# Moo_Digital.net
KiCad netlist of a schematic drawn in Altium Designer
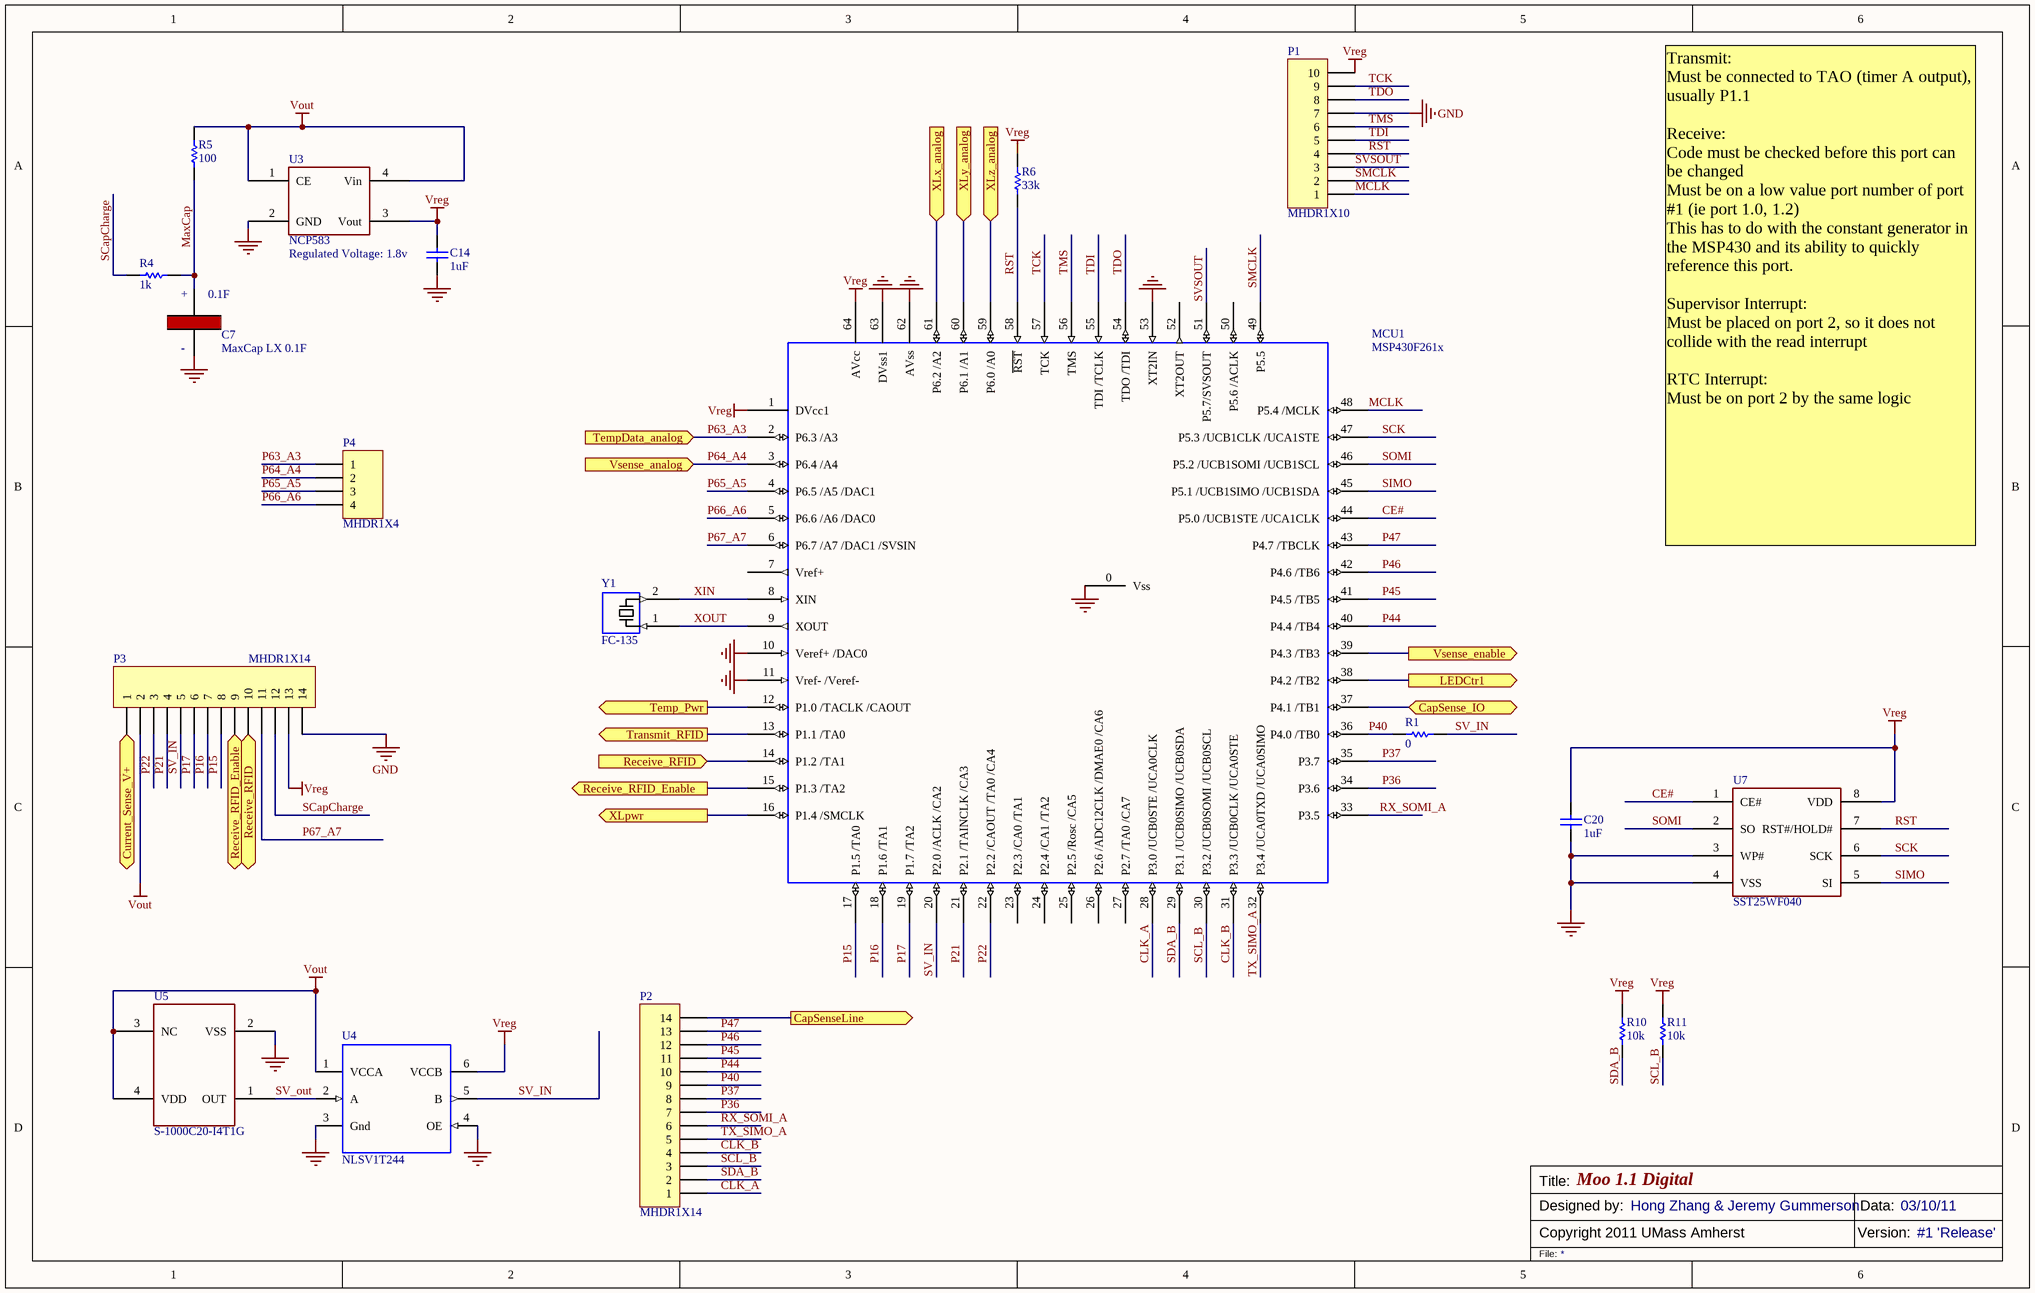
[diagram p0: Moo_Digital.SchDoc]

(export (version "E")
  (design (tool "Eeschema 10.0.6"))
  (components
    (comp (ref "C7")
      (value "MaxCap LX 0.1F")
      (footprint "Maxcap LX 0.1F")
      (description "MaxCap LX 0.1F, low leakage supper cap 5.5v")
      (libsource (lib "WispLib") (part "MaxCap LX 0.1F"))
    )
    (comp (ref "C14")
      (value "1uF")
      (footprint "WispLib:0402")
      (description "Ceramic Capacitor - Standard")
      (fields (field (name "Comment") "Ceramic_Chip_Capacitor"))
      (libsource (lib "WispLib") (part "Ceramic_Chip_Capacitor"))
    )
    (comp (ref "C20")
      (value "1uF")
      (footprint "WispLib:0402")
      (description "Ceramic Capacitor - Standard")
      (fields (field (name "Comment") "Ceramic_Chip_Capacitor"))
      (libsource (lib "WispLib") (part "Ceramic_Chip_Capacitor"))
    )
    (comp (ref "MCU1")
      (value "MSP430F261x")
      (footprint "64-PM")
      (description "64PM MSP430F261x")
      (libsource (lib "WispLib") (part "MSP430F261x"))
    )
    (comp (ref "P1")
      (value "MHDR1X10")
      (footprint "MHDR1X10")
      (description "Header, 10-Pin")
      (fields (field (name "PUBLISHER") "Altium Limited"))
      (libsource (lib "Miscellaneous Connectors") (part "MHDR1X10"))
    )
    (comp (ref "P2")
      (value "MHDR1X14")
      (footprint "MHDR1X14")
      (description "Header, 14-Pin")
      (fields (field (name "PUBLISHER") "Altium Limited"))
      (libsource (lib "") (part "MHDR1X14_1"))
    )
    (comp (ref "P3")
      (value "MHDR1X14")
      (footprint "MHDR1X14")
      (description "Header, 14-Pin")
      (fields (field (name "PUBLISHER") "Altium Limited"))
      (libsource (lib "Miscellaneous Connectors") (part "MHDR1X14"))
    )
    (comp (ref "P4")
      (value "MHDR1X4")
      (footprint "MHDR1X4")
      (description "Header, 4-Pin")
      (fields (field (name "PUBLISHER") "Altium Limited"))
      (libsource (lib "Miscellaneous Connectors") (part "MHDR1X4"))
    )
    (comp (ref "R1")
      (value "0")
      (footprint "WispLib:0402")
      (description "Thick Film Chip Resistor")
      (libsource (lib "*") (part "Thick Film Chip Resistor"))
    )
    (comp (ref "R4")
      (value "1k")
      (footprint "WispLib:0402")
      (description "Thick Film Chip Resistor")
      (libsource (lib "*") (part "Thick Film Chip Resistor"))
    )
    (comp (ref "R5")
      (value "100")
      (footprint "WispLib:0402")
      (description "Thick Film Chip Resistor")
      (libsource (lib "*") (part "Thick Film Chip Resistor"))
    )
    (comp (ref "R6")
      (value "33k")
      (footprint "WispLib:0402")
      (description "Thick Film Chip Resistor")
      (libsource (lib "*") (part "Thick Film Chip Resistor"))
    )
    (comp (ref "R10")
      (value "10k")
      (footprint "WispLib:0402")
      (description "Thick Film Chip Resistor")
      (libsource (lib "*") (part "Thick Film Chip Resistor"))
    )
    (comp (ref "R11")
      (value "10k")
      (footprint "WispLib:0402")
      (description "Thick Film Chip Resistor")
      (libsource (lib "*") (part "Thick Film Chip Resistor"))
    )
    (comp (ref "U3")
      (value "NCP583")
      (footprint "SC82-AB")
      (description "Ultra-Low Iq 150mA CMOS LDO Regulator with Enable")
      (fields (field (name "REGULATED VOLTAGE") "1.8v"))
      (libsource (lib "*") (part "NCP583"))
    )
    (comp (ref "U4")
      (value "NLSV1T244")
      (footprint "UDFN6")
      (description "Level Shifter: 1-Bit Dual-Supply Non-Inverting Level Translator")
      (fields (field (name "PART NUMBER") "ADG3301"))
      (libsource (lib "WispLib") (part "NLSV1T244"))
    )
    (comp (ref "U5")
      (value "S-1000C20-I4T1G")
      (footprint "SNT-4A")
      (libsource (lib "WispLib") (part "S-1000C20-I4T"))
    )
    (comp (ref "U7")
      (value "SST25WF040")
      (footprint "SOIC8")
      (description "Serial Flash Memory - 8 Lead SOIC Package")
      (libsource (lib "WispLib") (part "SST25WF040"))
    )
    (comp (ref "Y1") (value "FC-135") (footprint "FC-135") (libsource (lib "WispLib") (part "FC-135")))
  )
  (nets
    (net (code "1") (name "/CE#") (class "Default")
      (node (ref "MCU1") (pin "44") (pinfunction "P5.0_/UCB1STE_/UCA1CLK_44") (pintype "bidirectional"))
      (node (ref "U7") (pin "1") (pinfunction "CE#_1") (pintype "passive"))
    )
    (net (code "2") (name "/CLK_A") (class "Default")
      (node (ref "MCU1") (pin "28") (pinfunction "P3.0_/UCB0STE_/UCA0CLK_28") (pintype "bidirectional"))
      (node (ref "P2") (pin "1") (pinfunction "1_1") (pintype "passive"))
    )
    (net (code "3") (name "/CLK_B") (class "Default")
      (node (ref "MCU1") (pin "31") (pinfunction "P3.3_/UCB0CLK_/UCA0STE_31") (pintype "bidirectional"))
      (node (ref "P2") (pin "4") (pinfunction "4_4") (pintype "passive"))
    )
    (net (code "4") (name "/CapSenseLine") (class "Default")
      (node (ref "P2") (pin "14") (pinfunction "14_14") (pintype "passive"))
    )
    (net (code "5") (name "/CapSense_IO") (class "Default")
      (node (ref "MCU1") (pin "37") (pinfunction "P4.1_/TB1_37") (pintype "bidirectional"))
    )
    (net (code "6") (name "/Current_Sense_V+") (class "Default")
      (node (ref "P3") (pin "1") (pinfunction "1_1") (pintype "passive"))
    )
    (net (code "7") (name "/LEDCtr1") (class "Default")
      (node (ref "MCU1") (pin "38") (pinfunction "P4.2_/TB2_38") (pintype "bidirectional"))
    )
    (net (code "8") (name "/MCLK") (class "Default")
      (node (ref "MCU1") (pin "48") (pinfunction "P5.4_/MCLK_48") (pintype "bidirectional"))
      (node (ref "P1") (pin "1") (pinfunction "1_1") (pintype "passive"))
    )
    (net (code "9") (name "/MaxCap") (class "Default")
      (node (ref "C7") (pin "1") (pinfunction "Positive_1") (pintype "power_in"))
      (node (ref "R4") (pin "1") (pinfunction "1_1") (pintype "passive"))
      (node (ref "R5") (pin "1") (pinfunction "1_1") (pintype "passive"))
    )
    (net (code "10") (name "/P15") (class "Default")
      (node (ref "MCU1") (pin "17") (pinfunction "P1.5_/TA0_17") (pintype "bidirectional"))
      (node (ref "P3") (pin "8") (pinfunction "8_8") (pintype "passive"))
    )
    (net (code "11") (name "/P16") (class "Default")
      (node (ref "MCU1") (pin "18") (pinfunction "P1.6_/TA1_18") (pintype "bidirectional"))
      (node (ref "P3") (pin "7") (pinfunction "7_7") (pintype "passive"))
    )
    (net (code "12") (name "/P17") (class "Default")
      (node (ref "MCU1") (pin "19") (pinfunction "P1.7_/TA2_19") (pintype "bidirectional"))
      (node (ref "P3") (pin "6") (pinfunction "6_6") (pintype "passive"))
    )
    (net (code "13") (name "/P21") (class "Default")
      (node (ref "MCU1") (pin "21") (pinfunction "P2.1_/TAINCLK_/CA3_21") (pintype "bidirectional"))
      (node (ref "P3") (pin "4") (pinfunction "4_4") (pintype "passive"))
    )
    (net (code "14") (name "/P22") (class "Default")
      (node (ref "MCU1") (pin "22") (pinfunction "P2.2_/CAOUT_/TA0_/CA4_22") (pintype "bidirectional"))
      (node (ref "P3") (pin "3") (pinfunction "3_3") (pintype "passive"))
    )
    (net (code "15") (name "/P36") (class "Default")
      (node (ref "MCU1") (pin "34") (pinfunction "P3.6_34") (pintype "bidirectional"))
      (node (ref "P2") (pin "7") (pinfunction "7_7") (pintype "passive"))
    )
    (net (code "16") (name "/P37") (class "Default")
      (node (ref "MCU1") (pin "35") (pinfunction "P3.7_35") (pintype "bidirectional"))
      (node (ref "P2") (pin "8") (pinfunction "8_8") (pintype "passive"))
    )
    (net (code "17") (name "/P40") (class "Default")
      (node (ref "MCU1") (pin "36") (pinfunction "P4.0_/TB0_36") (pintype "bidirectional"))
      (node (ref "P2") (pin "9") (pinfunction "9_9") (pintype "passive"))
      (node (ref "R1") (pin "2") (pinfunction "2_2") (pintype "passive"))
    )
    (net (code "18") (name "/P44") (class "Default")
      (node (ref "MCU1") (pin "40") (pinfunction "P4.4_/TB4_40") (pintype "bidirectional"))
      (node (ref "P2") (pin "10") (pinfunction "10_10") (pintype "passive"))
    )
    (net (code "19") (name "/P45") (class "Default")
      (node (ref "MCU1") (pin "41") (pinfunction "P4.5_/TB5_41") (pintype "bidirectional"))
      (node (ref "P2") (pin "11") (pinfunction "11_11") (pintype "passive"))
    )
    (net (code "20") (name "/P46") (class "Default")
      (node (ref "MCU1") (pin "42") (pinfunction "P4.6_/TB6_42") (pintype "bidirectional"))
      (node (ref "P2") (pin "12") (pinfunction "12_12") (pintype "passive"))
    )
    (net (code "21") (name "/P47") (class "Default")
      (node (ref "MCU1") (pin "43") (pinfunction "P4.7_/TBCLK_43") (pintype "bidirectional"))
      (node (ref "P2") (pin "13") (pinfunction "13_13") (pintype "passive"))
    )
    (net (code "22") (name "/P63_A3") (class "Default")
      (node (ref "MCU1") (pin "2") (pinfunction "P6.3_/A3_2") (pintype "bidirectional"))
      (node (ref "P4") (pin "1") (pinfunction "1_1") (pintype "passive"))
    )
    (net (code "23") (name "/P64_A4") (class "Default")
      (node (ref "MCU1") (pin "3") (pinfunction "P6.4_/A4_3") (pintype "bidirectional"))
      (node (ref "P4") (pin "2") (pinfunction "2_2") (pintype "passive"))
    )
    (net (code "24") (name "/P65_A5") (class "Default")
      (node (ref "MCU1") (pin "4") (pinfunction "P6.5_/A5_/DAC1_4") (pintype "bidirectional"))
      (node (ref "P4") (pin "3") (pinfunction "3_3") (pintype "passive"))
    )
    (net (code "25") (name "/P66_A6") (class "Default")
      (node (ref "MCU1") (pin "5") (pinfunction "P6.6_/A6_/DAC0_5") (pintype "bidirectional"))
      (node (ref "P4") (pin "4") (pinfunction "4_4") (pintype "passive"))
    )
    (net (code "26") (name "/P67_A7") (class "Default")
      (node (ref "MCU1") (pin "6") (pinfunction "P6.7_/A7_/DAC1_/SVSIN_6") (pintype "bidirectional"))
      (node (ref "P3") (pin "11") (pinfunction "11_11") (pintype "passive"))
    )
    (net (code "27") (name "/RST") (class "Default")
      (node (ref "MCU1") (pin "58") (pinfunction "~{RST}_58") (pintype "input"))
      (node (ref "P1") (pin "4") (pinfunction "4_4") (pintype "passive"))
      (node (ref "R6") (pin "2") (pinfunction "2_2") (pintype "passive"))
      (node (ref "U7") (pin "7") (pinfunction "RST#/HOLD#_7") (pintype "passive"))
    )
    (net (code "28") (name "/RX_SOMI_A") (class "Default")
      (node (ref "MCU1") (pin "33") (pinfunction "P3.5_33") (pintype "bidirectional"))
      (node (ref "P2") (pin "6") (pinfunction "6_6") (pintype "passive"))
    )
    (net (code "29") (name "/Receive_RFID") (class "Default")
      (node (ref "MCU1") (pin "14") (pinfunction "P1.2_/TA1_14") (pintype "bidirectional"))
      (node (ref "P3") (pin "10") (pinfunction "10_10") (pintype "passive"))
    )
    (net (code "30") (name "/Receive_RFID_Enable") (class "Default")
      (node (ref "MCU1") (pin "15") (pinfunction "P1.3_/TA2_15") (pintype "bidirectional"))
      (node (ref "P3") (pin "9") (pinfunction "9_9") (pintype "passive"))
    )
    (net (code "31") (name "/SCK") (class "Default")
      (node (ref "MCU1") (pin "47") (pinfunction "P5.3_/UCB1CLK_/UCA1STE_47") (pintype "bidirectional"))
      (node (ref "U7") (pin "6") (pinfunction "SCK_6") (pintype "passive"))
    )
    (net (code "32") (name "/SCL_B") (class "Default")
      (node (ref "MCU1") (pin "30") (pinfunction "P3.2_/UCB0SOMI_/UCB0SCL_30") (pintype "bidirectional"))
      (node (ref "P2") (pin "3") (pinfunction "3_3") (pintype "passive"))
      (node (ref "R11") (pin "2") (pinfunction "2_2") (pintype "passive"))
    )
    (net (code "33") (name "/SCapCharge") (class "Default")
      (node (ref "P3") (pin "12") (pinfunction "12_12") (pintype "passive"))
      (node (ref "R4") (pin "2") (pinfunction "2_2") (pintype "passive"))
    )
    (net (code "34") (name "/SDA_B") (class "Default")
      (node (ref "MCU1") (pin "29") (pinfunction "P3.1_/UCB0SIMO_/UCB0SDA_29") (pintype "bidirectional"))
      (node (ref "P2") (pin "2") (pinfunction "2_2") (pintype "passive"))
      (node (ref "R10") (pin "2") (pinfunction "2_2") (pintype "passive"))
    )
    (net (code "35") (name "/SIMO") (class "Default")
      (node (ref "MCU1") (pin "45") (pinfunction "P5.1_/UCB1SIMO_/UCB1SDA_45") (pintype "bidirectional"))
      (node (ref "U7") (pin "5") (pinfunction "SI_5") (pintype "passive"))
    )
    (net (code "36") (name "/SMCLK") (class "Default")
      (node (ref "MCU1") (pin "49") (pinfunction "P5.5_49") (pintype "bidirectional"))
      (node (ref "P1") (pin "2") (pinfunction "2_2") (pintype "passive"))
    )
    (net (code "37") (name "/SOMI") (class "Default")
      (node (ref "MCU1") (pin "46") (pinfunction "P5.2_/UCB1SOMI_/UCB1SCL_46") (pintype "bidirectional"))
      (node (ref "U7") (pin "2") (pinfunction "SO_2") (pintype "passive"))
    )
    (net (code "38") (name "/SVSOUT") (class "Default")
      (node (ref "MCU1") (pin "51") (pinfunction "P5.7/SVSOUT_51") (pintype "bidirectional"))
      (node (ref "P1") (pin "3") (pinfunction "3_3") (pintype "passive"))
    )
    (net (code "39") (name "/SV_IN") (class "Default")
      (node (ref "MCU1") (pin "20") (pinfunction "P2.0_/ACLK_/CA2_20") (pintype "bidirectional"))
      (node (ref "P3") (pin "5") (pinfunction "5_5") (pintype "passive"))
      (node (ref "R1") (pin "1") (pinfunction "1_1") (pintype "passive"))
      (node (ref "U4") (pin "5") (pinfunction "B_5") (pintype "output"))
    )
    (net (code "40") (name "/SV_out") (class "Default")
      (node (ref "U4") (pin "2") (pinfunction "A_2") (pintype "input"))
      (node (ref "U5") (pin "1") (pinfunction "OUT_1") (pintype "passive"))
    )
    (net (code "41") (name "/TCK") (class "Default")
      (node (ref "MCU1") (pin "57") (pinfunction "TCK_57") (pintype "input"))
      (node (ref "P1") (pin "9") (pinfunction "9_9") (pintype "passive"))
    )
    (net (code "42") (name "/TDI") (class "Default")
      (node (ref "MCU1") (pin "55") (pinfunction "TDI_/TCLK_55") (pintype "input"))
      (node (ref "P1") (pin "5") (pinfunction "5_5") (pintype "passive"))
    )
    (net (code "43") (name "/TDO") (class "Default")
      (node (ref "MCU1") (pin "54") (pinfunction "TDO_/TDI_54") (pintype "bidirectional"))
      (node (ref "P1") (pin "8") (pinfunction "8_8") (pintype "passive"))
    )
    (net (code "44") (name "/TMS") (class "Default")
      (node (ref "MCU1") (pin "56") (pinfunction "TMS_56") (pintype "input"))
      (node (ref "P1") (pin "6") (pinfunction "6_6") (pintype "passive"))
    )
    (net (code "45") (name "/TX_SIMO_A") (class "Default")
      (node (ref "MCU1") (pin "32") (pinfunction "P3.4_/UCA0TXD_/UCA0SIMO_32") (pintype "bidirectional"))
      (node (ref "P2") (pin "5") (pinfunction "5_5") (pintype "passive"))
    )
    (net (code "46") (name "/Temp_Pwr") (class "Default")
      (node (ref "MCU1") (pin "12") (pinfunction "P1.0_/TACLK_/CAOUT_12") (pintype "bidirectional"))
    )
    (net (code "47") (name "/Transmit_RFID") (class "Default")
      (node (ref "MCU1") (pin "13") (pinfunction "P1.1_/TA0_13") (pintype "bidirectional"))
    )
    (net (code "48") (name "/Vsense_enable") (class "Default")
      (node (ref "MCU1") (pin "39") (pinfunction "P4.3_/TB3_39") (pintype "bidirectional"))
    )
    (net (code "49") (name "/XIN") (class "Default")
      (node (ref "MCU1") (pin "8") (pinfunction "XIN_8") (pintype "input"))
      (node (ref "Y1") (pin "2") (pinfunction "2_2") (pintype "output"))
    )
    (net (code "50") (name "/XLpwr") (class "Default")
      (node (ref "MCU1") (pin "16") (pinfunction "P1.4_/SMCLK_16") (pintype "bidirectional"))
    )
    (net (code "51") (name "/XLx_analog") (class "Default")
      (node (ref "MCU1") (pin "61") (pinfunction "P6.2_/A2_61") (pintype "bidirectional"))
    )
    (net (code "52") (name "/XLy_analog") (class "Default")
      (node (ref "MCU1") (pin "60") (pinfunction "P6.1_/A1_60") (pintype "bidirectional"))
    )
    (net (code "53") (name "/XLz_analog") (class "Default")
      (node (ref "MCU1") (pin "59") (pinfunction "P6.0_/A0_59") (pintype "bidirectional"))
    )
    (net (code "54") (name "/XOUT") (class "Default")
      (node (ref "MCU1") (pin "9") (pinfunction "XOUT_9") (pintype "output"))
      (node (ref "Y1") (pin "1") (pinfunction "1_1") (pintype "input"))
    )
    (net (code "55") (name "GND") (class "Default")
      (node (ref "C14") (pin "1") (pinfunction "1_1") (pintype "passive"))
      (node (ref "C20") (pin "2") (pinfunction "2_2") (pintype "passive"))
      (node (ref "C7") (pin "2") (pinfunction "GND_2") (pintype "power_in"))
      (node (ref "MCU1") (pin "0") (pinfunction "Vss_0") (pintype "power_in"))
      (node (ref "MCU1") (pin "10") (pinfunction "Veref+_/DAC0_10") (pintype "input"))
      (node (ref "MCU1") (pin "11") (pinfunction "Vref-_/Veref-_11") (pintype "input"))
      (node (ref "MCU1") (pin "53") (pinfunction "XT2IN_53") (pintype "input"))
      (node (ref "MCU1") (pin "62") (pinfunction "AVss_62") (pintype "power_in"))
      (node (ref "MCU1") (pin "63") (pinfunction "DVss1_63") (pintype "power_in"))
      (node (ref "P1") (pin "7") (pinfunction "7_7") (pintype "passive"))
      (node (ref "P3") (pin "14") (pinfunction "14_14") (pintype "passive"))
      (node (ref "U3") (pin "2") (pinfunction "GND_2") (pintype "passive"))
      (node (ref "U4") (pin "3") (pinfunction "Gnd_3") (pintype "power_in"))
      (node (ref "U4") (pin "4") (pinfunction "OE_4") (pintype "input"))
      (node (ref "U5") (pin "2") (pinfunction "VSS_2") (pintype "passive"))
      (node (ref "U7") (pin "3") (pinfunction "WP#_3") (pintype "passive"))
      (node (ref "U7") (pin "4") (pinfunction "VSS_4") (pintype "passive"))
    )
    (net (code "56") (name "Vout") (class "Default")
      (node (ref "P3") (pin "2") (pinfunction "2_2") (pintype "passive"))
      (node (ref "R5") (pin "2") (pinfunction "2_2") (pintype "passive"))
      (node (ref "U3") (pin "1") (pinfunction "CE_1") (pintype "passive"))
      (node (ref "U3") (pin "4") (pinfunction "Vin_4") (pintype "passive"))
      (node (ref "U4") (pin "1") (pinfunction "VCCA_1") (pintype "power_in"))
      (node (ref "U5") (pin "3") (pinfunction "NC_3") (pintype "passive"))
      (node (ref "U5") (pin "4") (pinfunction "VDD_4") (pintype "passive"))
    )
    (net (code "57") (name "Vreg") (class "Default")
      (node (ref "C14") (pin "2") (pinfunction "2_2") (pintype "passive"))
      (node (ref "C20") (pin "1") (pinfunction "1_1") (pintype "passive"))
      (node (ref "MCU1") (pin "1") (pinfunction "DVcc1_1") (pintype "power_in"))
      (node (ref "MCU1") (pin "64") (pinfunction "AVcc_64") (pintype "power_in"))
      (node (ref "P1") (pin "10") (pinfunction "10_10") (pintype "passive"))
      (node (ref "P3") (pin "13") (pinfunction "13_13") (pintype "passive"))
      (node (ref "R10") (pin "1") (pinfunction "1_1") (pintype "passive"))
      (node (ref "R11") (pin "1") (pinfunction "1_1") (pintype "passive"))
      (node (ref "R6") (pin "1") (pinfunction "1_1") (pintype "passive"))
      (node (ref "U3") (pin "3") (pinfunction "Vout_3") (pintype "passive"))
      (node (ref "U4") (pin "6") (pinfunction "VCCB_6") (pintype "power_in"))
      (node (ref "U7") (pin "8") (pinfunction "VDD_8") (pintype "passive"))
    )
    (net (code "58") (name "unconnected-(MCU1-P2.3_{slash}CA0_{slash}TA1-Pad23)") (class "Default")
      (node (ref "MCU1") (pin "23") (pinfunction "P2.3_/CA0_/TA1_23") (pintype "bidirectional"))
    )
    (net (code "59") (name "unconnected-(MCU1-P2.4_{slash}CA1_{slash}TA2-Pad24)") (class "Default")
      (node (ref "MCU1") (pin "24") (pinfunction "P2.4_/CA1_/TA2_24") (pintype "bidirectional"))
    )
    (net (code "60") (name "unconnected-(MCU1-P2.5_{slash}Rosc_{slash}CA5-Pad25)") (class "Default")
      (node (ref "MCU1") (pin "25") (pinfunction "P2.5_/Rosc_/CA5_25") (pintype "bidirectional"))
    )
    (net (code "61") (name "unconnected-(MCU1-P2.6_{slash}ADC12CLK_{slash}DMAE0_{slash}CA6-Pad26)") (class "Default")
      (node (ref "MCU1") (pin "26") (pinfunction "P2.6_/ADC12CLK_/DMAE0_/CA6_26") (pintype "bidirectional"))
    )
    (net (code "62") (name "unconnected-(MCU1-P2.7_{slash}TA0_{slash}CA7-Pad27)") (class "Default")
      (node (ref "MCU1") (pin "27") (pinfunction "P2.7_/TA0_/CA7_27") (pintype "bidirectional"))
    )
    (net (code "63") (name "unconnected-(MCU1-P5.6_{slash}ACLK-Pad50)") (class "Default")
      (node (ref "MCU1") (pin "50") (pinfunction "P5.6_/ACLK_50") (pintype "bidirectional"))
    )
    (net (code "64") (name "unconnected-(MCU1-Vref+-Pad7)") (class "Default")
      (node (ref "MCU1") (pin "7") (pinfunction "Vref+_7") (pintype "output"))
    )
    (net (code "65") (name "unconnected-(MCU1-XT2OUT-Pad52)") (class "Default")
      (node (ref "MCU1") (pin "52") (pinfunction "XT2OUT_52") (pintype "output"))
    )
  )
)
